# pc_pulse_v3.net
KiCad netlist of a schematic drawn in EAGLE
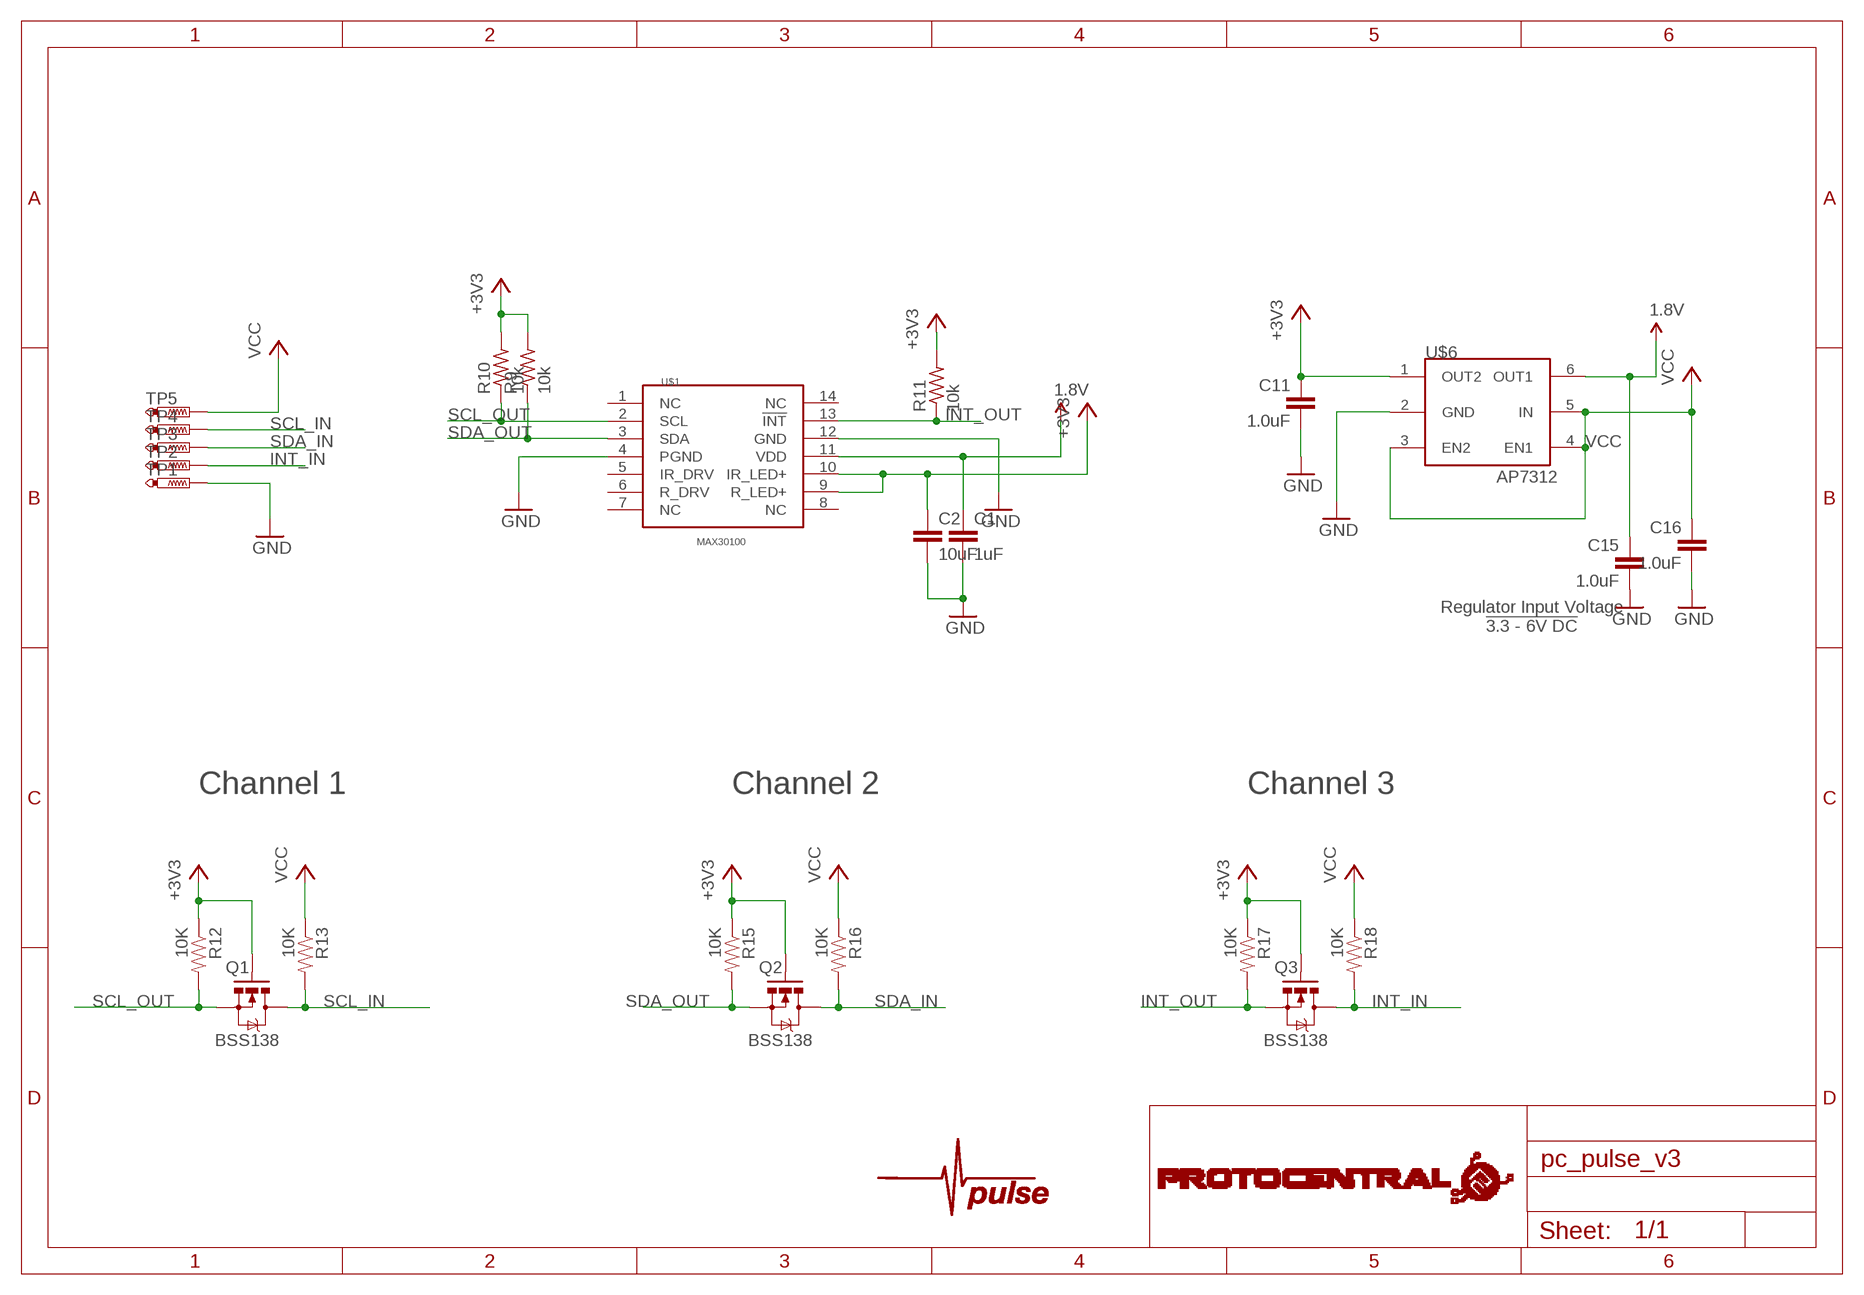
[diagram p0: schematic, sheet 1]

(export (version "E")
  (design (tool "Eeschema 10.0.6"))
  (components
    (comp (ref "C1")
      (value "1uF")
      (footprint "eagle-import:C0805")
      (libsource (lib "eagle-import") (part "C-EUC0805"))
    )
    (comp (ref "C2")
      (value "10uF")
      (footprint "eagle-import:C0805")
      (libsource (lib "eagle-import") (part "C-EUC0805"))
    )
    (comp (ref "C11")
      (value "1.0uF")
      (footprint "eagle-import:0805")
      (libsource (lib "eagle-import") (part "1.0UF-0805-25V-10%"))
    )
    (comp (ref "C15")
      (value "1.0uF")
      (footprint "eagle-import:0805")
      (libsource (lib "eagle-import") (part "1.0UF-0805-25V-10%"))
    )
    (comp (ref "C16")
      (value "1.0uF")
      (footprint "eagle-import:0805")
      (libsource (lib "eagle-import") (part "1.0UF-0805-25V-10%"))
    )
    (comp (ref "Q1")
      (value "BSS138")
      (footprint "eagle-import:SOT23-3")
      (libsource (lib "eagle-import") (part "MOSFET-NCHANNELSMD"))
    )
    (comp (ref "Q2")
      (value "BSS138")
      (footprint "eagle-import:SOT23-3")
      (libsource (lib "eagle-import") (part "MOSFET-NCHANNELSMD"))
    )
    (comp (ref "Q3")
      (value "BSS138")
      (footprint "eagle-import:SOT23-3")
      (libsource (lib "eagle-import") (part "MOSFET-NCHANNELSMD"))
    )
    (comp (ref "R9")
      (value "10k")
      (footprint "eagle-import:R0402")
      (libsource (lib "eagle-import") (part "R-US_R0402"))
    )
    (comp (ref "R10")
      (value "10k")
      (footprint "eagle-import:R0402")
      (libsource (lib "eagle-import") (part "R-US_R0402"))
    )
    (comp (ref "R11")
      (value "10k")
      (footprint "eagle-import:R0402")
      (libsource (lib "eagle-import") (part "R-US_R0402"))
    )
    (comp (ref "R12")
      (value "10K")
      (footprint "eagle-import:0402-RES")
      (libsource (lib "eagle-import") (part "RESISTOR0402-RES"))
    )
    (comp (ref "R13")
      (value "10K")
      (footprint "eagle-import:0402-RES")
      (libsource (lib "eagle-import") (part "RESISTOR0402-RES"))
    )
    (comp (ref "R15")
      (value "10K")
      (footprint "eagle-import:0402-RES")
      (libsource (lib "eagle-import") (part "RESISTOR0402-RES"))
    )
    (comp (ref "R16")
      (value "10K")
      (footprint "eagle-import:0402-RES")
      (libsource (lib "eagle-import") (part "RESISTOR0402-RES"))
    )
    (comp (ref "R17")
      (value "10K")
      (footprint "eagle-import:0402-RES")
      (libsource (lib "eagle-import") (part "RESISTOR0402-RES"))
    )
    (comp (ref "R18")
      (value "10K")
      (footprint "eagle-import:0402-RES")
      (libsource (lib "eagle-import") (part "RESISTOR0402-RES"))
    )
    (comp (ref "TP1")
      (value "PTR1TP20SQ")
      (footprint "eagle-import:TP20SQ")
      (libsource (lib "eagle-import") (part "PTR1TP20SQ"))
    )
    (comp (ref "TP2")
      (value "PTR1TP20SQ")
      (footprint "eagle-import:TP20SQ")
      (libsource (lib "eagle-import") (part "PTR1TP20SQ"))
    )
    (comp (ref "TP3")
      (value "PTR1TP20SQ")
      (footprint "eagle-import:TP20SQ")
      (libsource (lib "eagle-import") (part "PTR1TP20SQ"))
    )
    (comp (ref "TP4")
      (value "PTR1TP20SQ")
      (footprint "eagle-import:TP20SQ")
      (libsource (lib "eagle-import") (part "PTR1TP20SQ"))
    )
    (comp (ref "TP5")
      (value "PTR1TP20SQ")
      (footprint "eagle-import:TP20SQ")
      (libsource (lib "eagle-import") (part "PTR1TP20SQ"))
    )
    (comp (ref "U$1")
      (value "MAX30100")
      (footprint "eagle-import:OESIP-14")
      (libsource (lib "eagle-import") (part "MAX30100"))
    )
    (comp (ref "U$3")
      (value "PROTY-LOGO")
      (footprint "eagle-import:LOGO-PROTY")
      (libsource (lib "eagle-import") (part "PROTY-LOGO"))
    )
    (comp (ref "U$4")
      (value "PULSE")
      (footprint "eagle-import:PULSE")
      (libsource (lib "eagle-import") (part "PULSE"))
    )
    (comp (ref "U$6")
      (value "AP7312")
      (footprint "eagle-import:SOT26")
      (libsource (lib "eagle-import") (part "AP7312"))
    )
    (comp (ref "U$7")
      (value "PROTY_LOGO_WITH_TEXT")
      (footprint "eagle-import:PROTY_WITH_TEXT")
      (libsource (lib "eagle-import") (part "PROTY_LOGO_WITH_TEXT"))
    )
  )
  (nets
    (net (code "1") (name "+3V3") (class "Default")
      (node (ref "C11") (pin "1") (pinfunction "1_1") (pintype "passive"))
      (node (ref "C2") (pin "1") (pinfunction "1_1") (pintype "passive"))
      (node (ref "Q1") (pin "1") (pinfunction "G_1") (pintype "passive"))
      (node (ref "Q2") (pin "1") (pinfunction "G_1") (pintype "passive"))
      (node (ref "Q3") (pin "1") (pinfunction "G_1") (pintype "passive"))
      (node (ref "R10") (pin "2") (pinfunction "2_2") (pintype "passive"))
      (node (ref "R11") (pin "2") (pinfunction "2_2") (pintype "passive"))
      (node (ref "R12") (pin "1") (pinfunction "1_1") (pintype "passive"))
      (node (ref "R15") (pin "1") (pinfunction "1_1") (pintype "passive"))
      (node (ref "R17") (pin "1") (pinfunction "1_1") (pintype "passive"))
      (node (ref "R9") (pin "2") (pinfunction "2_2") (pintype "passive"))
      (node (ref "U$1") (pin "10") (pinfunction "IR_LED+_10") (pintype "bidirectional"))
      (node (ref "U$1") (pin "9") (pinfunction "R_LED+_9") (pintype "bidirectional"))
      (node (ref "U$6") (pin "1") (pinfunction "OUT2_1") (pintype "bidirectional"))
    )
    (net (code "2") (name "/INT_IN") (class "Default")
      (node (ref "Q3") (pin "3") (pinfunction "D_3") (pintype "passive"))
      (node (ref "R18") (pin "2") (pinfunction "2_2") (pintype "passive"))
      (node (ref "TP2") (pin "TP") (pinfunction "TP_TP") (pintype "input"))
    )
    (net (code "3") (name "/INT_OUT") (class "Default")
      (node (ref "Q3") (pin "2") (pinfunction "S_2") (pintype "passive"))
      (node (ref "R11") (pin "1") (pinfunction "1_1") (pintype "passive"))
      (node (ref "R17") (pin "2") (pinfunction "2_2") (pintype "passive"))
      (node (ref "U$1") (pin "13") (pinfunction "~{INT}_13") (pintype "bidirectional"))
    )
    (net (code "4") (name "/SCL_IN") (class "Default")
      (node (ref "Q1") (pin "3") (pinfunction "D_3") (pintype "passive"))
      (node (ref "R13") (pin "2") (pinfunction "2_2") (pintype "passive"))
      (node (ref "TP4") (pin "TP") (pinfunction "TP_TP") (pintype "input"))
    )
    (net (code "5") (name "/SCL_OUT") (class "Default")
      (node (ref "Q1") (pin "2") (pinfunction "S_2") (pintype "passive"))
      (node (ref "R10") (pin "1") (pinfunction "1_1") (pintype "passive"))
      (node (ref "R12") (pin "2") (pinfunction "2_2") (pintype "passive"))
      (node (ref "U$1") (pin "2") (pinfunction "SCL_2") (pintype "bidirectional"))
    )
    (net (code "6") (name "/SDA_IN") (class "Default")
      (node (ref "Q2") (pin "3") (pinfunction "D_3") (pintype "passive"))
      (node (ref "R16") (pin "2") (pinfunction "2_2") (pintype "passive"))
      (node (ref "TP3") (pin "TP") (pinfunction "TP_TP") (pintype "input"))
    )
    (net (code "7") (name "/SDA_OUT") (class "Default")
      (node (ref "Q2") (pin "2") (pinfunction "S_2") (pintype "passive"))
      (node (ref "R15") (pin "2") (pinfunction "2_2") (pintype "passive"))
      (node (ref "R9") (pin "1") (pinfunction "1_1") (pintype "passive"))
      (node (ref "U$1") (pin "3") (pinfunction "SDA_3") (pintype "bidirectional"))
    )
    (net (code "8") (name "1.8V") (class "Default")
      (node (ref "C1") (pin "1") (pinfunction "1_1") (pintype "passive"))
      (node (ref "C15") (pin "1") (pinfunction "1_1") (pintype "passive"))
      (node (ref "U$1") (pin "11") (pinfunction "VDD_11") (pintype "bidirectional"))
      (node (ref "U$6") (pin "6") (pinfunction "OUT1_6") (pintype "bidirectional"))
    )
    (net (code "9") (name "GND") (class "Default")
      (node (ref "C1") (pin "2") (pinfunction "2_2") (pintype "passive"))
      (node (ref "C11") (pin "2") (pinfunction "2_2") (pintype "passive"))
      (node (ref "C15") (pin "2") (pinfunction "2_2") (pintype "passive"))
      (node (ref "C16") (pin "2") (pinfunction "2_2") (pintype "passive"))
      (node (ref "C2") (pin "2") (pinfunction "2_2") (pintype "passive"))
      (node (ref "TP1") (pin "TP") (pinfunction "TP_TP") (pintype "input"))
      (node (ref "U$1") (pin "12") (pinfunction "GND_12") (pintype "bidirectional"))
      (node (ref "U$1") (pin "4") (pinfunction "PGND_4") (pintype "bidirectional"))
      (node (ref "U$6") (pin "2") (pinfunction "GND_2") (pintype "bidirectional"))
    )
    (net (code "10") (name "VCC") (class "Default")
      (node (ref "C16") (pin "1") (pinfunction "1_1") (pintype "passive"))
      (node (ref "R13") (pin "1") (pinfunction "1_1") (pintype "passive"))
      (node (ref "R16") (pin "1") (pinfunction "1_1") (pintype "passive"))
      (node (ref "R18") (pin "1") (pinfunction "1_1") (pintype "passive"))
      (node (ref "TP5") (pin "TP") (pinfunction "TP_TP") (pintype "input"))
      (node (ref "U$6") (pin "3") (pinfunction "EN2_3") (pintype "bidirectional"))
      (node (ref "U$6") (pin "4") (pinfunction "EN1_4") (pintype "bidirectional"))
      (node (ref "U$6") (pin "5") (pinfunction "IN_5") (pintype "bidirectional"))
    )
    (net (code "11") (name "unconnected-(U$1-IR_DRV-Pad5)") (class "Default")
      (node (ref "U$1") (pin "5") (pinfunction "IR_DRV_5") (pintype "bidirectional"))
    )
    (net (code "12") (name "unconnected-(U$1-NC-Pad1)") (class "Default")
      (node (ref "U$1") (pin "1") (pinfunction "NC_1") (pintype "bidirectional"))
    )
    (net (code "13") (name "unconnected-(U$1-NC-Pad7)") (class "Default")
      (node (ref "U$1") (pin "7") (pinfunction "NC_7") (pintype "bidirectional"))
    )
    (net (code "14") (name "unconnected-(U$1-NC-Pad8)") (class "Default")
      (node (ref "U$1") (pin "8") (pinfunction "NC_8") (pintype "bidirectional"))
    )
    (net (code "15") (name "unconnected-(U$1-NC-Pad14)") (class "Default")
      (node (ref "U$1") (pin "14") (pinfunction "NC_14") (pintype "bidirectional"))
    )
    (net (code "16") (name "unconnected-(U$1-R_DRV-Pad6)") (class "Default")
      (node (ref "U$1") (pin "6") (pinfunction "R_DRV_6") (pintype "bidirectional"))
    )
  )
)
